# LED_matrix.net
KiCad netlist of a schematic drawn in Altium Designer
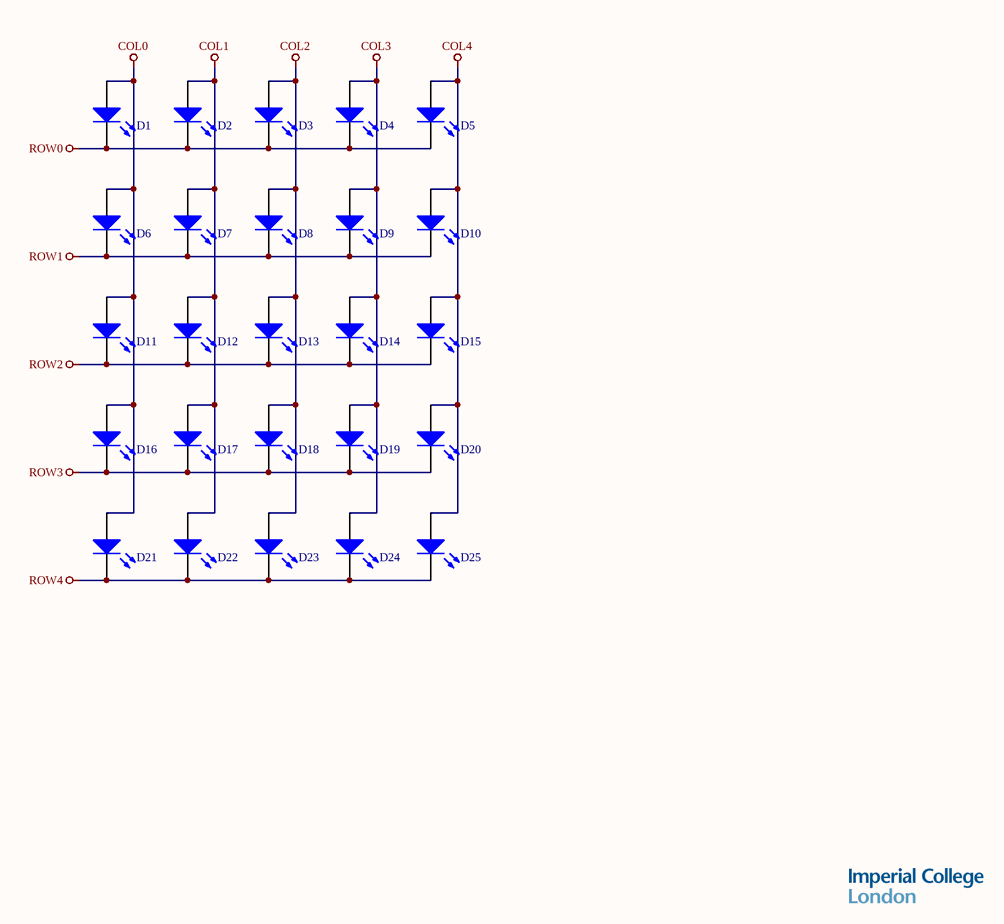
[diagram p0: LED matrix.SchDoc]

(export (version "E")
  (design (tool "Eeschema 10.0.6"))
  (components
    (comp (ref "D1")
      (value "LED")
      (footprint "PCB-pjce6c538hbnjhyboevm-1")
      (description "L-793SRD-E, Round Series Red LED, 640 nm 8 mm, Round Lens Through Hole package")
      (fields (field (name "MANUFACTURER PART NUMBER") "L-793SRD-E"))
      (libsource (lib "CommunityVault") (part "CMP-c7440e1cac271883-2"))
    )
    (comp (ref "D2")
      (value "LED")
      (footprint "PCB-pjce6c538hbnjhyboevm-1")
      (description "L-793SRD-E, Round Series Red LED, 640 nm 8 mm, Round Lens Through Hole package")
      (fields (field (name "MANUFACTURER PART NUMBER") "L-793SRD-E"))
      (libsource (lib "CommunityVault") (part "SYM-c7440e1cac271883-1"))
    )
    (comp (ref "D3")
      (value "LED")
      (footprint "PCB-pjce6c538hbnjhyboevm-1")
      (description "L-793SRD-E, Round Series Red LED, 640 nm 8 mm, Round Lens Through Hole package")
      (fields (field (name "MANUFACTURER PART NUMBER") "L-793SRD-E"))
      (libsource (lib "CommunityVault") (part "SYM-c7440e1cac271883-1"))
    )
    (comp (ref "D4")
      (value "LED")
      (footprint "PCB-pjce6c538hbnjhyboevm-1")
      (description "L-793SRD-E, Round Series Red LED, 640 nm 8 mm, Round Lens Through Hole package")
      (fields (field (name "MANUFACTURER PART NUMBER") "L-793SRD-E"))
      (libsource (lib "CommunityVault") (part "SYM-c7440e1cac271883-1"))
    )
    (comp (ref "D5")
      (value "LED")
      (footprint "PCB-pjce6c538hbnjhyboevm-1")
      (description "L-793SRD-E, Round Series Red LED, 640 nm 8 mm, Round Lens Through Hole package")
      (fields (field (name "MANUFACTURER PART NUMBER") "L-793SRD-E"))
      (libsource (lib "CommunityVault") (part "SYM-c7440e1cac271883-1"))
    )
    (comp (ref "D6")
      (value "LED")
      (footprint "PCB-pjce6c538hbnjhyboevm-1")
      (description "L-793SRD-E, Round Series Red LED, 640 nm 8 mm, Round Lens Through Hole package")
      (fields (field (name "MANUFACTURER PART NUMBER") "L-793SRD-E"))
      (libsource (lib "CommunityVault") (part "SYM-c7440e1cac271883-1"))
    )
    (comp (ref "D7")
      (value "LED")
      (footprint "PCB-pjce6c538hbnjhyboevm-1")
      (description "L-793SRD-E, Round Series Red LED, 640 nm 8 mm, Round Lens Through Hole package")
      (fields (field (name "MANUFACTURER PART NUMBER") "L-793SRD-E"))
      (libsource (lib "CommunityVault") (part "SYM-c7440e1cac271883-1"))
    )
    (comp (ref "D8")
      (value "LED")
      (footprint "PCB-pjce6c538hbnjhyboevm-1")
      (description "L-793SRD-E, Round Series Red LED, 640 nm 8 mm, Round Lens Through Hole package")
      (fields (field (name "MANUFACTURER PART NUMBER") "L-793SRD-E"))
      (libsource (lib "CommunityVault") (part "SYM-c7440e1cac271883-1"))
    )
    (comp (ref "D9")
      (value "LED")
      (footprint "PCB-pjce6c538hbnjhyboevm-1")
      (description "L-793SRD-E, Round Series Red LED, 640 nm 8 mm, Round Lens Through Hole package")
      (fields (field (name "MANUFACTURER PART NUMBER") "L-793SRD-E"))
      (libsource (lib "CommunityVault") (part "SYM-c7440e1cac271883-1"))
    )
    (comp (ref "D10")
      (value "LED")
      (footprint "PCB-pjce6c538hbnjhyboevm-1")
      (description "L-793SRD-E, Round Series Red LED, 640 nm 8 mm, Round Lens Through Hole package")
      (fields (field (name "MANUFACTURER PART NUMBER") "L-793SRD-E"))
      (libsource (lib "CommunityVault") (part "SYM-c7440e1cac271883-1"))
    )
    (comp (ref "D11")
      (value "LED")
      (footprint "PCB-pjce6c538hbnjhyboevm-1")
      (description "L-793SRD-E, Round Series Red LED, 640 nm 8 mm, Round Lens Through Hole package")
      (fields (field (name "MANUFACTURER PART NUMBER") "L-793SRD-E"))
      (libsource (lib "CommunityVault") (part "SYM-c7440e1cac271883-1"))
    )
    (comp (ref "D12")
      (value "LED")
      (footprint "PCB-pjce6c538hbnjhyboevm-1")
      (description "L-793SRD-E, Round Series Red LED, 640 nm 8 mm, Round Lens Through Hole package")
      (fields (field (name "MANUFACTURER PART NUMBER") "L-793SRD-E"))
      (libsource (lib "CommunityVault") (part "SYM-c7440e1cac271883-1"))
    )
    (comp (ref "D13")
      (value "LED")
      (footprint "PCB-pjce6c538hbnjhyboevm-1")
      (description "L-793SRD-E, Round Series Red LED, 640 nm 8 mm, Round Lens Through Hole package")
      (fields (field (name "MANUFACTURER PART NUMBER") "L-793SRD-E"))
      (libsource (lib "CommunityVault") (part "SYM-c7440e1cac271883-1"))
    )
    (comp (ref "D14")
      (value "LED")
      (footprint "PCB-pjce6c538hbnjhyboevm-1")
      (description "L-793SRD-E, Round Series Red LED, 640 nm 8 mm, Round Lens Through Hole package")
      (fields (field (name "MANUFACTURER PART NUMBER") "L-793SRD-E"))
      (libsource (lib "CommunityVault") (part "SYM-c7440e1cac271883-1"))
    )
    (comp (ref "D15")
      (value "LED")
      (footprint "PCB-pjce6c538hbnjhyboevm-1")
      (description "L-793SRD-E, Round Series Red LED, 640 nm 8 mm, Round Lens Through Hole package")
      (fields (field (name "MANUFACTURER PART NUMBER") "L-793SRD-E"))
      (libsource (lib "CommunityVault") (part "SYM-c7440e1cac271883-1"))
    )
    (comp (ref "D16")
      (value "LED")
      (footprint "PCB-pjce6c538hbnjhyboevm-1")
      (description "L-793SRD-E, Round Series Red LED, 640 nm 8 mm, Round Lens Through Hole package")
      (fields (field (name "MANUFACTURER PART NUMBER") "L-793SRD-E"))
      (libsource (lib "CommunityVault") (part "SYM-c7440e1cac271883-1"))
    )
    (comp (ref "D17")
      (value "LED")
      (footprint "PCB-pjce6c538hbnjhyboevm-1")
      (description "L-793SRD-E, Round Series Red LED, 640 nm 8 mm, Round Lens Through Hole package")
      (fields (field (name "MANUFACTURER PART NUMBER") "L-793SRD-E"))
      (libsource (lib "CommunityVault") (part "SYM-c7440e1cac271883-1"))
    )
    (comp (ref "D18")
      (value "LED")
      (footprint "PCB-pjce6c538hbnjhyboevm-1")
      (description "L-793SRD-E, Round Series Red LED, 640 nm 8 mm, Round Lens Through Hole package")
      (fields (field (name "MANUFACTURER PART NUMBER") "L-793SRD-E"))
      (libsource (lib "CommunityVault") (part "SYM-c7440e1cac271883-1"))
    )
    (comp (ref "D19")
      (value "LED")
      (footprint "PCB-pjce6c538hbnjhyboevm-1")
      (description "L-793SRD-E, Round Series Red LED, 640 nm 8 mm, Round Lens Through Hole package")
      (fields (field (name "MANUFACTURER PART NUMBER") "L-793SRD-E"))
      (libsource (lib "CommunityVault") (part "SYM-c7440e1cac271883-1"))
    )
    (comp (ref "D20")
      (value "LED")
      (footprint "PCB-pjce6c538hbnjhyboevm-1")
      (description "L-793SRD-E, Round Series Red LED, 640 nm 8 mm, Round Lens Through Hole package")
      (fields (field (name "MANUFACTURER PART NUMBER") "L-793SRD-E"))
      (libsource (lib "CommunityVault") (part "SYM-c7440e1cac271883-1"))
    )
    (comp (ref "D21")
      (value "LED")
      (footprint "PCB-pjce6c538hbnjhyboevm-1")
      (description "L-793SRD-E, Round Series Red LED, 640 nm 8 mm, Round Lens Through Hole package")
      (fields (field (name "MANUFACTURER PART NUMBER") "L-793SRD-E"))
      (libsource (lib "CommunityVault") (part "SYM-c7440e1cac271883-1"))
    )
    (comp (ref "D22")
      (value "LED")
      (footprint "PCB-pjce6c538hbnjhyboevm-1")
      (description "L-793SRD-E, Round Series Red LED, 640 nm 8 mm, Round Lens Through Hole package")
      (fields (field (name "MANUFACTURER PART NUMBER") "L-793SRD-E"))
      (libsource (lib "CommunityVault") (part "SYM-c7440e1cac271883-1"))
    )
    (comp (ref "D23")
      (value "LED")
      (footprint "PCB-pjce6c538hbnjhyboevm-1")
      (description "L-793SRD-E, Round Series Red LED, 640 nm 8 mm, Round Lens Through Hole package")
      (fields (field (name "MANUFACTURER PART NUMBER") "L-793SRD-E"))
      (libsource (lib "CommunityVault") (part "SYM-c7440e1cac271883-1"))
    )
    (comp (ref "D24")
      (value "LED")
      (footprint "PCB-pjce6c538hbnjhyboevm-1")
      (description "L-793SRD-E, Round Series Red LED, 640 nm 8 mm, Round Lens Through Hole package")
      (fields (field (name "MANUFACTURER PART NUMBER") "L-793SRD-E"))
      (libsource (lib "CommunityVault") (part "CMP-c7440e1cac271883-2"))
    )
    (comp (ref "D25")
      (value "LED")
      (footprint "PCB-pjce6c538hbnjhyboevm-1")
      (description "L-793SRD-E, Round Series Red LED, 640 nm 8 mm, Round Lens Through Hole package")
      (fields (field (name "MANUFACTURER PART NUMBER") "L-793SRD-E"))
      (libsource (lib "CommunityVault") (part "SYM-c7440e1cac271883-1"))
    )
  )
  (nets
    (net (code "1") (name "COL0") (class "Default")
      (node (ref "D1") (pin "1") (pinfunction "A_1") (pintype "passive"))
      (node (ref "D11") (pin "1") (pinfunction "A_1") (pintype "passive"))
      (node (ref "D16") (pin "1") (pinfunction "A_1") (pintype "passive"))
      (node (ref "D21") (pin "1") (pinfunction "A_1") (pintype "passive"))
      (node (ref "D6") (pin "1") (pinfunction "A_1") (pintype "passive"))
    )
    (net (code "2") (name "COL1") (class "Default")
      (node (ref "D12") (pin "1") (pinfunction "A_1") (pintype "passive"))
      (node (ref "D17") (pin "1") (pinfunction "A_1") (pintype "passive"))
      (node (ref "D2") (pin "1") (pinfunction "A_1") (pintype "passive"))
      (node (ref "D22") (pin "1") (pinfunction "A_1") (pintype "passive"))
      (node (ref "D7") (pin "1") (pinfunction "A_1") (pintype "passive"))
    )
    (net (code "3") (name "COL2") (class "Default")
      (node (ref "D13") (pin "1") (pinfunction "A_1") (pintype "passive"))
      (node (ref "D18") (pin "1") (pinfunction "A_1") (pintype "passive"))
      (node (ref "D23") (pin "1") (pinfunction "A_1") (pintype "passive"))
      (node (ref "D3") (pin "1") (pinfunction "A_1") (pintype "passive"))
      (node (ref "D8") (pin "1") (pinfunction "A_1") (pintype "passive"))
    )
    (net (code "4") (name "COL3") (class "Default")
      (node (ref "D14") (pin "1") (pinfunction "A_1") (pintype "passive"))
      (node (ref "D19") (pin "1") (pinfunction "A_1") (pintype "passive"))
      (node (ref "D24") (pin "1") (pinfunction "A_1") (pintype "passive"))
      (node (ref "D4") (pin "1") (pinfunction "A_1") (pintype "passive"))
      (node (ref "D9") (pin "1") (pinfunction "A_1") (pintype "passive"))
    )
    (net (code "5") (name "COL4") (class "Default")
      (node (ref "D10") (pin "1") (pinfunction "A_1") (pintype "passive"))
      (node (ref "D15") (pin "1") (pinfunction "A_1") (pintype "passive"))
      (node (ref "D20") (pin "1") (pinfunction "A_1") (pintype "passive"))
      (node (ref "D25") (pin "1") (pinfunction "A_1") (pintype "passive"))
      (node (ref "D5") (pin "1") (pinfunction "A_1") (pintype "passive"))
    )
    (net (code "6") (name "ROW0") (class "Default")
      (node (ref "D1") (pin "2") (pinfunction "K_2") (pintype "passive"))
      (node (ref "D2") (pin "2") (pinfunction "K_2") (pintype "passive"))
      (node (ref "D3") (pin "2") (pinfunction "K_2") (pintype "passive"))
      (node (ref "D4") (pin "2") (pinfunction "K_2") (pintype "passive"))
      (node (ref "D5") (pin "2") (pinfunction "K_2") (pintype "passive"))
    )
    (net (code "7") (name "ROW1") (class "Default")
      (node (ref "D10") (pin "2") (pinfunction "K_2") (pintype "passive"))
      (node (ref "D6") (pin "2") (pinfunction "K_2") (pintype "passive"))
      (node (ref "D7") (pin "2") (pinfunction "K_2") (pintype "passive"))
      (node (ref "D8") (pin "2") (pinfunction "K_2") (pintype "passive"))
      (node (ref "D9") (pin "2") (pinfunction "K_2") (pintype "passive"))
    )
    (net (code "8") (name "ROW2") (class "Default")
      (node (ref "D11") (pin "2") (pinfunction "K_2") (pintype "passive"))
      (node (ref "D12") (pin "2") (pinfunction "K_2") (pintype "passive"))
      (node (ref "D13") (pin "2") (pinfunction "K_2") (pintype "passive"))
      (node (ref "D14") (pin "2") (pinfunction "K_2") (pintype "passive"))
      (node (ref "D15") (pin "2") (pinfunction "K_2") (pintype "passive"))
    )
    (net (code "9") (name "ROW3") (class "Default")
      (node (ref "D16") (pin "2") (pinfunction "K_2") (pintype "passive"))
      (node (ref "D17") (pin "2") (pinfunction "K_2") (pintype "passive"))
      (node (ref "D18") (pin "2") (pinfunction "K_2") (pintype "passive"))
      (node (ref "D19") (pin "2") (pinfunction "K_2") (pintype "passive"))
      (node (ref "D20") (pin "2") (pinfunction "K_2") (pintype "passive"))
    )
    (net (code "10") (name "ROW4") (class "Default")
      (node (ref "D21") (pin "2") (pinfunction "K_2") (pintype "passive"))
      (node (ref "D22") (pin "2") (pinfunction "K_2") (pintype "passive"))
      (node (ref "D23") (pin "2") (pinfunction "K_2") (pintype "passive"))
      (node (ref "D24") (pin "2") (pinfunction "K_2") (pintype "passive"))
      (node (ref "D25") (pin "2") (pinfunction "K_2") (pintype "passive"))
    )
  )
)
